# vtf-schem-v1.net
KiCad netlist of a schematic drawn in Altium Designer
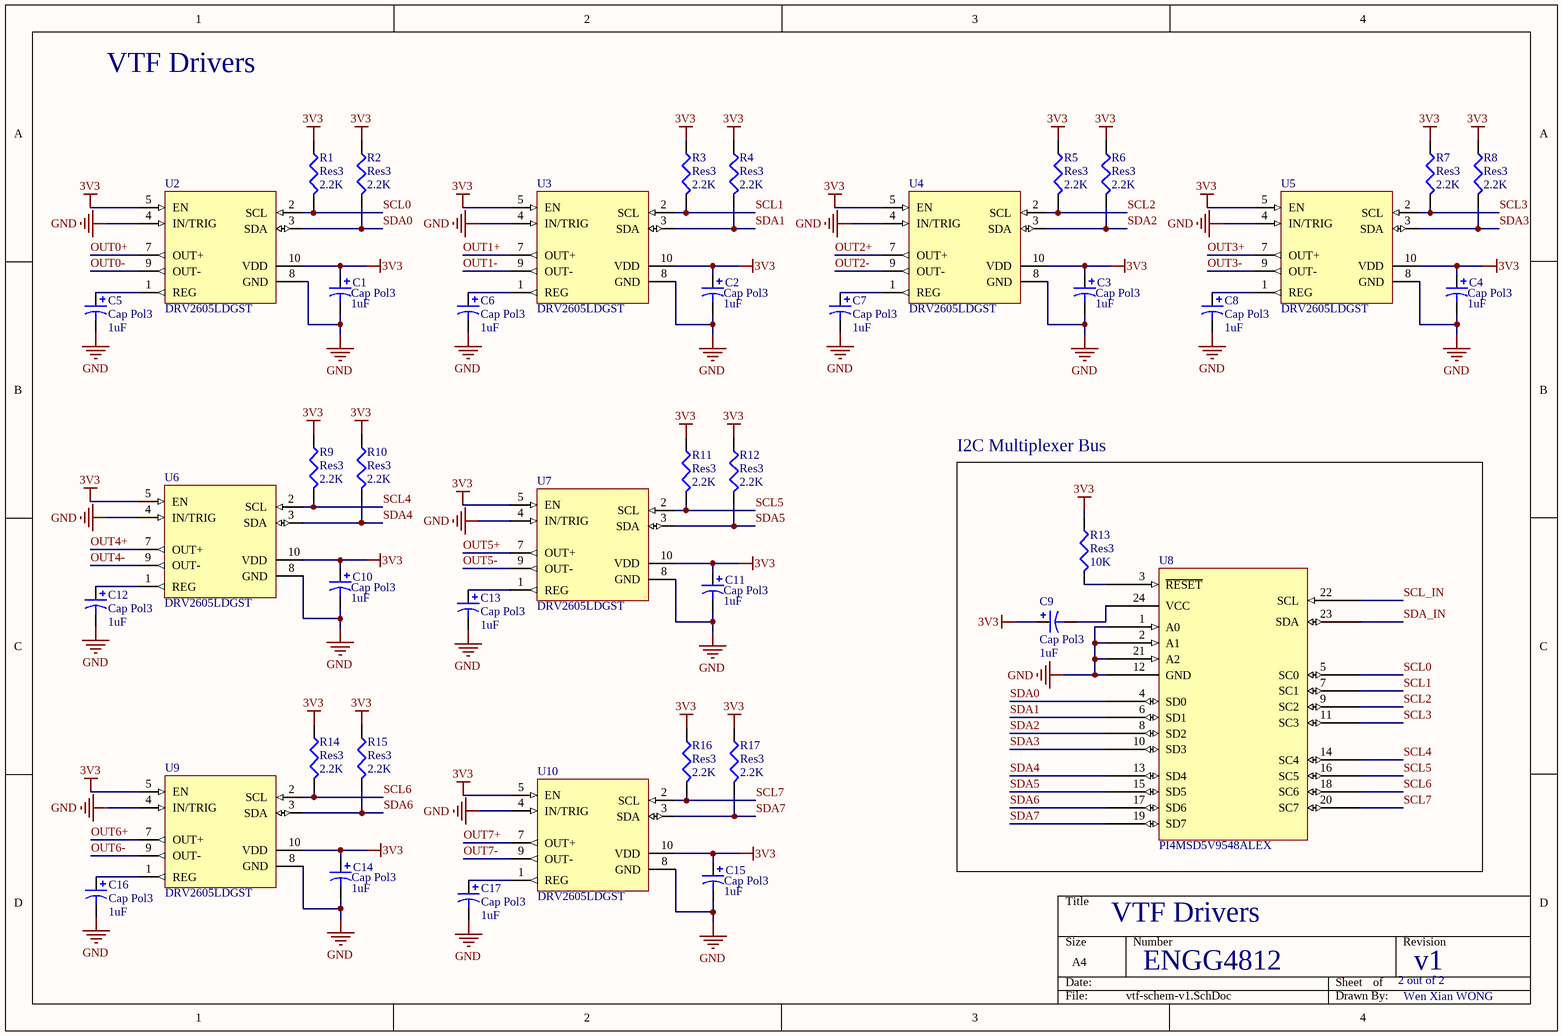
[diagram p0: vtf-schem-v1.SchDoc]

(export (version "E")
  (design (tool "Eeschema 10.0.6"))
  (components
    (comp (ref "C1")
      (value "Cap Pol3")
      (footprint "0402")
      (description "Polarized Capacitor (Surface Mount)")
      (fields (field (name "ALTIUM_VALUE") "1uF") (field (name "PUBLISHER") "Altium Limited"))
      (libsource (lib "Miscellaneous Devices") (part "Cap Pol3"))
    )
    (comp (ref "C2")
      (value "Cap Pol3")
      (footprint "0402")
      (description "Polarized Capacitor (Surface Mount)")
      (fields (field (name "ALTIUM_VALUE") "1uF") (field (name "PUBLISHER") "Altium Limited"))
      (libsource (lib "Miscellaneous Devices") (part "Cap Pol3"))
    )
    (comp (ref "C3")
      (value "Cap Pol3")
      (footprint "0402")
      (description "Polarized Capacitor (Surface Mount)")
      (fields (field (name "ALTIUM_VALUE") "1uF") (field (name "PUBLISHER") "Altium Limited"))
      (libsource (lib "Miscellaneous Devices") (part "Cap Pol3"))
    )
    (comp (ref "C4")
      (value "Cap Pol3")
      (footprint "0402")
      (description "Polarized Capacitor (Surface Mount)")
      (fields (field (name "ALTIUM_VALUE") "1uF") (field (name "PUBLISHER") "Altium Limited"))
      (libsource (lib "Miscellaneous Devices") (part "Cap Pol3"))
    )
    (comp (ref "C5")
      (value "Cap Pol3")
      (footprint "0402")
      (description "Polarized Capacitor (Surface Mount)")
      (fields (field (name "ALTIUM_VALUE") "1uF") (field (name "PUBLISHER") "Altium Limited"))
      (libsource (lib "Miscellaneous Devices") (part "Cap Pol3"))
    )
    (comp (ref "C6")
      (value "Cap Pol3")
      (footprint "0402")
      (description "Polarized Capacitor (Surface Mount)")
      (fields (field (name "ALTIUM_VALUE") "1uF") (field (name "PUBLISHER") "Altium Limited"))
      (libsource (lib "Miscellaneous Devices") (part "Cap Pol3"))
    )
    (comp (ref "C7")
      (value "Cap Pol3")
      (footprint "0402")
      (description "Polarized Capacitor (Surface Mount)")
      (fields (field (name "ALTIUM_VALUE") "1uF") (field (name "PUBLISHER") "Altium Limited"))
      (libsource (lib "Miscellaneous Devices") (part "Cap Pol3"))
    )
    (comp (ref "C8")
      (value "Cap Pol3")
      (footprint "0402")
      (description "Polarized Capacitor (Surface Mount)")
      (fields (field (name "ALTIUM_VALUE") "1uF") (field (name "PUBLISHER") "Altium Limited"))
      (libsource (lib "Miscellaneous Devices") (part "Cap Pol3"))
    )
    (comp (ref "C9")
      (value "Cap Pol3")
      (footprint "0402")
      (description "Polarized Capacitor (Surface Mount)")
      (fields (field (name "ALTIUM_VALUE") "1uF") (field (name "PUBLISHER") "Altium Limited"))
      (libsource (lib "Miscellaneous Devices") (part "Cap Pol3"))
    )
    (comp (ref "C10")
      (value "Cap Pol3")
      (footprint "0402")
      (description "Polarized Capacitor (Surface Mount)")
      (fields (field (name "ALTIUM_VALUE") "1uF") (field (name "PUBLISHER") "Altium Limited"))
      (libsource (lib "Miscellaneous Devices") (part "Cap Pol3"))
    )
    (comp (ref "C11")
      (value "Cap Pol3")
      (footprint "0402")
      (description "Polarized Capacitor (Surface Mount)")
      (fields (field (name "ALTIUM_VALUE") "1uF") (field (name "PUBLISHER") "Altium Limited"))
      (libsource (lib "Miscellaneous Devices") (part "Cap Pol3"))
    )
    (comp (ref "C12")
      (value "Cap Pol3")
      (footprint "0402")
      (description "Polarized Capacitor (Surface Mount)")
      (fields (field (name "ALTIUM_VALUE") "1uF") (field (name "PUBLISHER") "Altium Limited"))
      (libsource (lib "Miscellaneous Devices") (part "Cap Pol3"))
    )
    (comp (ref "C13")
      (value "Cap Pol3")
      (footprint "0402")
      (description "Polarized Capacitor (Surface Mount)")
      (fields (field (name "ALTIUM_VALUE") "1uF") (field (name "PUBLISHER") "Altium Limited"))
      (libsource (lib "Miscellaneous Devices") (part "Cap Pol3"))
    )
    (comp (ref "C14")
      (value "Cap Pol3")
      (footprint "0402")
      (description "Polarized Capacitor (Surface Mount)")
      (fields (field (name "ALTIUM_VALUE") "1uF") (field (name "PUBLISHER") "Altium Limited"))
      (libsource (lib "Miscellaneous Devices") (part "Cap Pol3"))
    )
    (comp (ref "C15")
      (value "Cap Pol3")
      (footprint "0402")
      (description "Polarized Capacitor (Surface Mount)")
      (fields (field (name "ALTIUM_VALUE") "1uF") (field (name "PUBLISHER") "Altium Limited"))
      (libsource (lib "Miscellaneous Devices") (part "Cap Pol3"))
    )
    (comp (ref "C16")
      (value "Cap Pol3")
      (footprint "0402")
      (description "Polarized Capacitor (Surface Mount)")
      (fields (field (name "ALTIUM_VALUE") "1uF") (field (name "PUBLISHER") "Altium Limited"))
      (libsource (lib "Miscellaneous Devices") (part "Cap Pol3"))
    )
    (comp (ref "C17")
      (value "Cap Pol3")
      (footprint "0402")
      (description "Polarized Capacitor (Surface Mount)")
      (fields (field (name "ALTIUM_VALUE") "1uF") (field (name "PUBLISHER") "Altium Limited"))
      (libsource (lib "Miscellaneous Devices") (part "Cap Pol3"))
    )
    (comp (ref "R1")
      (value "Res3")
      (footprint "0402")
      (description "Resistor")
      (fields (field (name "ALTIUM_VALUE") "2.2K") (field (name "PUBLISHER") "Altium Limited"))
      (libsource (lib "Miscellaneous Devices") (part "Res3"))
    )
    (comp (ref "R2")
      (value "Res3")
      (footprint "0402")
      (description "Resistor")
      (fields (field (name "ALTIUM_VALUE") "2.2K") (field (name "PUBLISHER") "Altium Limited"))
      (libsource (lib "Miscellaneous Devices") (part "Res3"))
    )
    (comp (ref "R3")
      (value "Res3")
      (footprint "0402")
      (description "Resistor")
      (fields (field (name "ALTIUM_VALUE") "2.2K") (field (name "PUBLISHER") "Altium Limited"))
      (libsource (lib "Miscellaneous Devices") (part "Res3"))
    )
    (comp (ref "R4")
      (value "Res3")
      (footprint "0402")
      (description "Resistor")
      (fields (field (name "ALTIUM_VALUE") "2.2K") (field (name "PUBLISHER") "Altium Limited"))
      (libsource (lib "Miscellaneous Devices") (part "Res3"))
    )
    (comp (ref "R5")
      (value "Res3")
      (footprint "0402")
      (description "Resistor")
      (fields (field (name "ALTIUM_VALUE") "2.2K") (field (name "PUBLISHER") "Altium Limited"))
      (libsource (lib "Miscellaneous Devices") (part "Res3"))
    )
    (comp (ref "R6")
      (value "Res3")
      (footprint "0402")
      (description "Resistor")
      (fields (field (name "ALTIUM_VALUE") "2.2K") (field (name "PUBLISHER") "Altium Limited"))
      (libsource (lib "Miscellaneous Devices") (part "Res3"))
    )
    (comp (ref "R7")
      (value "Res3")
      (footprint "0402")
      (description "Resistor")
      (fields (field (name "ALTIUM_VALUE") "2.2K") (field (name "PUBLISHER") "Altium Limited"))
      (libsource (lib "Miscellaneous Devices") (part "Res3"))
    )
    (comp (ref "R8")
      (value "Res3")
      (footprint "0402")
      (description "Resistor")
      (fields (field (name "ALTIUM_VALUE") "2.2K") (field (name "PUBLISHER") "Altium Limited"))
      (libsource (lib "Miscellaneous Devices") (part "Res3"))
    )
    (comp (ref "R9")
      (value "Res3")
      (footprint "0402")
      (description "Resistor")
      (fields (field (name "ALTIUM_VALUE") "2.2K") (field (name "PUBLISHER") "Altium Limited"))
      (libsource (lib "Miscellaneous Devices") (part "Res3"))
    )
    (comp (ref "R10")
      (value "Res3")
      (footprint "0402")
      (description "Resistor")
      (fields (field (name "ALTIUM_VALUE") "2.2K") (field (name "PUBLISHER") "Altium Limited"))
      (libsource (lib "Miscellaneous Devices") (part "Res3"))
    )
    (comp (ref "R11")
      (value "Res3")
      (footprint "0402")
      (description "Resistor")
      (fields (field (name "ALTIUM_VALUE") "2.2K") (field (name "PUBLISHER") "Altium Limited"))
      (libsource (lib "Miscellaneous Devices") (part "Res3"))
    )
    (comp (ref "R12")
      (value "Res3")
      (footprint "0402")
      (description "Resistor")
      (fields (field (name "ALTIUM_VALUE") "2.2K") (field (name "PUBLISHER") "Altium Limited"))
      (libsource (lib "Miscellaneous Devices") (part "Res3"))
    )
    (comp (ref "R13")
      (value "Res3")
      (footprint "0402")
      (description "Resistor")
      (fields (field (name "ALTIUM_VALUE") "10K") (field (name "PUBLISHER") "Altium Limited"))
      (libsource (lib "Miscellaneous Devices") (part "Res3"))
    )
    (comp (ref "R14")
      (value "Res3")
      (footprint "0402")
      (description "Resistor")
      (fields (field (name "ALTIUM_VALUE") "2.2K") (field (name "PUBLISHER") "Altium Limited"))
      (libsource (lib "Miscellaneous Devices") (part "Res3"))
    )
    (comp (ref "R15")
      (value "Res3")
      (footprint "0402")
      (description "Resistor")
      (fields (field (name "ALTIUM_VALUE") "2.2K") (field (name "PUBLISHER") "Altium Limited"))
      (libsource (lib "Miscellaneous Devices") (part "Res3"))
    )
    (comp (ref "R16")
      (value "Res3")
      (footprint "0402")
      (description "Resistor")
      (fields (field (name "ALTIUM_VALUE") "2.2K") (field (name "PUBLISHER") "Altium Limited"))
      (libsource (lib "Miscellaneous Devices") (part "Res3"))
    )
    (comp (ref "R17")
      (value "Res3")
      (footprint "0402")
      (description "Resistor")
      (fields (field (name "ALTIUM_VALUE") "2.2K") (field (name "PUBLISHER") "Altium Limited"))
      (libsource (lib "Miscellaneous Devices") (part "Res3"))
    )
    (comp (ref "U2")
      (value "DRV2605LDGST")
      (footprint "Driver")
      (libsource (lib "Schlib1") (part "DRV2605LDGST"))
    )
    (comp (ref "U3")
      (value "DRV2605LDGST")
      (footprint "Driver")
      (libsource (lib "Schlib1") (part "DRV2605LDGST"))
    )
    (comp (ref "U4")
      (value "DRV2605LDGST")
      (footprint "Driver")
      (libsource (lib "Schlib1") (part "DRV2605LDGST"))
    )
    (comp (ref "U5")
      (value "DRV2605LDGST")
      (footprint "Driver")
      (libsource (lib "Schlib1") (part "DRV2605LDGST"))
    )
    (comp (ref "U6")
      (value "DRV2605LDGST")
      (footprint "Driver")
      (libsource (lib "Schlib1") (part "DRV2605LDGST"))
    )
    (comp (ref "U7")
      (value "DRV2605LDGST")
      (footprint "Driver")
      (libsource (lib "Schlib1") (part "DRV2605LDGST"))
    )
    (comp (ref "U8")
      (value "PI4MSD5V9548ALEX")
      (footprint "I2C bus")
      (libsource (lib "Schlib1") (part "I2C Bus"))
    )
    (comp (ref "U9")
      (value "DRV2605LDGST")
      (footprint "Driver")
      (libsource (lib "Schlib1") (part "DRV2605LDGST"))
    )
    (comp (ref "U10")
      (value "DRV2605LDGST")
      (footprint "Driver")
      (libsource (lib "Schlib1") (part "DRV2605LDGST"))
    )
  )
  (nets
    (net (code "1") (name "/OUT0+") (class "Default")
      (node (ref "U2") (pin "7") (pinfunction "OUT+_7") (pintype "output"))
    )
    (net (code "2") (name "/OUT0-") (class "Default")
      (node (ref "U2") (pin "9") (pinfunction "OUT-_9") (pintype "output"))
    )
    (net (code "3") (name "/OUT1+") (class "Default")
      (node (ref "U3") (pin "7") (pinfunction "OUT+_7") (pintype "output"))
    )
    (net (code "4") (name "/OUT1-") (class "Default")
      (node (ref "U3") (pin "9") (pinfunction "OUT-_9") (pintype "output"))
    )
    (net (code "5") (name "/OUT2+") (class "Default")
      (node (ref "U4") (pin "7") (pinfunction "OUT+_7") (pintype "output"))
    )
    (net (code "6") (name "/OUT2-") (class "Default")
      (node (ref "U4") (pin "9") (pinfunction "OUT-_9") (pintype "output"))
    )
    (net (code "7") (name "/OUT3+") (class "Default")
      (node (ref "U5") (pin "7") (pinfunction "OUT+_7") (pintype "output"))
    )
    (net (code "8") (name "/OUT3-") (class "Default")
      (node (ref "U5") (pin "9") (pinfunction "OUT-_9") (pintype "output"))
    )
    (net (code "9") (name "/OUT4+") (class "Default")
      (node (ref "U6") (pin "7") (pinfunction "OUT+_7") (pintype "output"))
    )
    (net (code "10") (name "/OUT4-") (class "Default")
      (node (ref "U6") (pin "9") (pinfunction "OUT-_9") (pintype "output"))
    )
    (net (code "11") (name "/OUT5+") (class "Default")
      (node (ref "U7") (pin "7") (pinfunction "OUT+_7") (pintype "output"))
    )
    (net (code "12") (name "/OUT5-") (class "Default")
      (node (ref "U7") (pin "9") (pinfunction "OUT-_9") (pintype "output"))
    )
    (net (code "13") (name "/OUT6+") (class "Default")
      (node (ref "U9") (pin "7") (pinfunction "OUT+_7") (pintype "output"))
    )
    (net (code "14") (name "/OUT6-") (class "Default")
      (node (ref "U9") (pin "9") (pinfunction "OUT-_9") (pintype "output"))
    )
    (net (code "15") (name "/OUT7+") (class "Default")
      (node (ref "U10") (pin "7") (pinfunction "OUT+_7") (pintype "output"))
    )
    (net (code "16") (name "/OUT7-") (class "Default")
      (node (ref "U10") (pin "9") (pinfunction "OUT-_9") (pintype "output"))
    )
    (net (code "17") (name "/SCL0") (class "Default")
      (node (ref "R1") (pin "2") (pinfunction "2_2") (pintype "passive"))
      (node (ref "U2") (pin "2") (pinfunction "SCL_2") (pintype "input"))
      (node (ref "U8") (pin "5") (pinfunction "SC0_5") (pintype "bidirectional"))
    )
    (net (code "18") (name "/SCL1") (class "Default")
      (node (ref "R3") (pin "2") (pinfunction "2_2") (pintype "passive"))
      (node (ref "U3") (pin "2") (pinfunction "SCL_2") (pintype "input"))
      (node (ref "U8") (pin "7") (pinfunction "SC1_7") (pintype "bidirectional"))
    )
    (net (code "19") (name "/SCL2") (class "Default")
      (node (ref "R5") (pin "2") (pinfunction "2_2") (pintype "passive"))
      (node (ref "U4") (pin "2") (pinfunction "SCL_2") (pintype "input"))
      (node (ref "U8") (pin "9") (pinfunction "SC2_9") (pintype "bidirectional"))
    )
    (net (code "20") (name "/SCL3") (class "Default")
      (node (ref "R7") (pin "2") (pinfunction "2_2") (pintype "passive"))
      (node (ref "U5") (pin "2") (pinfunction "SCL_2") (pintype "input"))
      (node (ref "U8") (pin "11") (pinfunction "SC3_11") (pintype "bidirectional"))
    )
    (net (code "21") (name "/SCL4") (class "Default")
      (node (ref "R9") (pin "2") (pinfunction "2_2") (pintype "passive"))
      (node (ref "U6") (pin "2") (pinfunction "SCL_2") (pintype "input"))
      (node (ref "U8") (pin "14") (pinfunction "SC4_14") (pintype "bidirectional"))
    )
    (net (code "22") (name "/SCL5") (class "Default")
      (node (ref "R11") (pin "2") (pinfunction "2_2") (pintype "passive"))
      (node (ref "U7") (pin "2") (pinfunction "SCL_2") (pintype "input"))
      (node (ref "U8") (pin "16") (pinfunction "SC5_16") (pintype "bidirectional"))
    )
    (net (code "23") (name "/SCL6") (class "Default")
      (node (ref "R14") (pin "2") (pinfunction "2_2") (pintype "passive"))
      (node (ref "U8") (pin "18") (pinfunction "SC6_18") (pintype "bidirectional"))
      (node (ref "U9") (pin "2") (pinfunction "SCL_2") (pintype "input"))
    )
    (net (code "24") (name "/SCL7") (class "Default")
      (node (ref "R16") (pin "2") (pinfunction "2_2") (pintype "passive"))
      (node (ref "U10") (pin "2") (pinfunction "SCL_2") (pintype "input"))
      (node (ref "U8") (pin "20") (pinfunction "SC7_20") (pintype "bidirectional"))
    )
    (net (code "25") (name "/SCL_IN") (class "Default")
      (node (ref "U8") (pin "22") (pinfunction "SCL_22") (pintype "input"))
    )
    (net (code "26") (name "/SDA0") (class "Default")
      (node (ref "R2") (pin "2") (pinfunction "2_2") (pintype "passive"))
      (node (ref "U2") (pin "3") (pinfunction "SDA_3") (pintype "bidirectional"))
      (node (ref "U8") (pin "4") (pinfunction "SD0_4") (pintype "bidirectional"))
    )
    (net (code "27") (name "/SDA1") (class "Default")
      (node (ref "R4") (pin "2") (pinfunction "2_2") (pintype "passive"))
      (node (ref "U3") (pin "3") (pinfunction "SDA_3") (pintype "bidirectional"))
      (node (ref "U8") (pin "6") (pinfunction "SD1_6") (pintype "bidirectional"))
    )
    (net (code "28") (name "/SDA2") (class "Default")
      (node (ref "R6") (pin "2") (pinfunction "2_2") (pintype "passive"))
      (node (ref "U4") (pin "3") (pinfunction "SDA_3") (pintype "bidirectional"))
      (node (ref "U8") (pin "8") (pinfunction "SD2_8") (pintype "bidirectional"))
    )
    (net (code "29") (name "/SDA3") (class "Default")
      (node (ref "R8") (pin "2") (pinfunction "2_2") (pintype "passive"))
      (node (ref "U5") (pin "3") (pinfunction "SDA_3") (pintype "bidirectional"))
      (node (ref "U8") (pin "10") (pinfunction "SD3_10") (pintype "bidirectional"))
    )
    (net (code "30") (name "/SDA4") (class "Default")
      (node (ref "R10") (pin "2") (pinfunction "2_2") (pintype "passive"))
      (node (ref "U6") (pin "3") (pinfunction "SDA_3") (pintype "bidirectional"))
      (node (ref "U8") (pin "13") (pinfunction "SD4_13") (pintype "bidirectional"))
    )
    (net (code "31") (name "/SDA5") (class "Default")
      (node (ref "R12") (pin "2") (pinfunction "2_2") (pintype "passive"))
      (node (ref "U7") (pin "3") (pinfunction "SDA_3") (pintype "bidirectional"))
      (node (ref "U8") (pin "15") (pinfunction "SD5_15") (pintype "bidirectional"))
    )
    (net (code "32") (name "/SDA6") (class "Default")
      (node (ref "R15") (pin "2") (pinfunction "2_2") (pintype "passive"))
      (node (ref "U8") (pin "17") (pinfunction "SD6_17") (pintype "bidirectional"))
      (node (ref "U9") (pin "3") (pinfunction "SDA_3") (pintype "bidirectional"))
    )
    (net (code "33") (name "/SDA7") (class "Default")
      (node (ref "R17") (pin "2") (pinfunction "2_2") (pintype "passive"))
      (node (ref "U10") (pin "3") (pinfunction "SDA_3") (pintype "bidirectional"))
      (node (ref "U8") (pin "19") (pinfunction "SD7_19") (pintype "bidirectional"))
    )
    (net (code "34") (name "/SDA_IN") (class "Default")
      (node (ref "U8") (pin "23") (pinfunction "SDA_23") (pintype "bidirectional"))
    )
    (net (code "35") (name "3V3") (class "Default")
      (node (ref "C1") (pin "1") (pinfunction "1_1") (pintype "passive"))
      (node (ref "C10") (pin "1") (pinfunction "1_1") (pintype "passive"))
      (node (ref "C11") (pin "1") (pinfunction "1_1") (pintype "passive"))
      (node (ref "C14") (pin "1") (pinfunction "1_1") (pintype "passive"))
      (node (ref "C15") (pin "1") (pinfunction "1_1") (pintype "passive"))
      (node (ref "C2") (pin "1") (pinfunction "1_1") (pintype "passive"))
      (node (ref "C3") (pin "1") (pinfunction "1_1") (pintype "passive"))
      (node (ref "C4") (pin "1") (pinfunction "1_1") (pintype "passive"))
      (node (ref "C9") (pin "1") (pinfunction "1_1") (pintype "passive"))
      (node (ref "R1") (pin "1") (pinfunction "1_1") (pintype "passive"))
      (node (ref "R10") (pin "1") (pinfunction "1_1") (pintype "passive"))
      (node (ref "R11") (pin "1") (pinfunction "1_1") (pintype "passive"))
      (node (ref "R12") (pin "1") (pinfunction "1_1") (pintype "passive"))
      (node (ref "R13") (pin "1") (pinfunction "1_1") (pintype "passive"))
      (node (ref "R14") (pin "1") (pinfunction "1_1") (pintype "passive"))
      (node (ref "R15") (pin "1") (pinfunction "1_1") (pintype "passive"))
      (node (ref "R16") (pin "1") (pinfunction "1_1") (pintype "passive"))
      (node (ref "R17") (pin "1") (pinfunction "1_1") (pintype "passive"))
      (node (ref "R2") (pin "1") (pinfunction "1_1") (pintype "passive"))
      (node (ref "R3") (pin "1") (pinfunction "1_1") (pintype "passive"))
      (node (ref "R4") (pin "1") (pinfunction "1_1") (pintype "passive"))
      (node (ref "R5") (pin "1") (pinfunction "1_1") (pintype "passive"))
      (node (ref "R6") (pin "1") (pinfunction "1_1") (pintype "passive"))
      (node (ref "R7") (pin "1") (pinfunction "1_1") (pintype "passive"))
      (node (ref "R8") (pin "1") (pinfunction "1_1") (pintype "passive"))
      (node (ref "R9") (pin "1") (pinfunction "1_1") (pintype "passive"))
      (node (ref "U10") (pin "10") (pinfunction "VDD_10") (pintype "power_in"))
      (node (ref "U10") (pin "5") (pinfunction "EN_5") (pintype "input"))
      (node (ref "U2") (pin "10") (pinfunction "VDD_10") (pintype "power_in"))
      (node (ref "U2") (pin "5") (pinfunction "EN_5") (pintype "input"))
      (node (ref "U3") (pin "10") (pinfunction "VDD_10") (pintype "power_in"))
      (node (ref "U3") (pin "5") (pinfunction "EN_5") (pintype "input"))
      (node (ref "U4") (pin "10") (pinfunction "VDD_10") (pintype "power_in"))
      (node (ref "U4") (pin "5") (pinfunction "EN_5") (pintype "input"))
      (node (ref "U5") (pin "10") (pinfunction "VDD_10") (pintype "power_in"))
      (node (ref "U5") (pin "5") (pinfunction "EN_5") (pintype "input"))
      (node (ref "U6") (pin "10") (pinfunction "VDD_10") (pintype "power_in"))
      (node (ref "U6") (pin "5") (pinfunction "EN_5") (pintype "input"))
      (node (ref "U7") (pin "10") (pinfunction "VDD_10") (pintype "power_in"))
      (node (ref "U7") (pin "5") (pinfunction "EN_5") (pintype "input"))
      (node (ref "U9") (pin "10") (pinfunction "VDD_10") (pintype "power_in"))
      (node (ref "U9") (pin "5") (pinfunction "EN_5") (pintype "input"))
    )
    (net (code "36") (name "GND") (class "Default")
      (node (ref "C1") (pin "2") (pinfunction "2_2") (pintype "passive"))
      (node (ref "C10") (pin "2") (pinfunction "2_2") (pintype "passive"))
      (node (ref "C11") (pin "2") (pinfunction "2_2") (pintype "passive"))
      (node (ref "C12") (pin "2") (pinfunction "2_2") (pintype "passive"))
      (node (ref "C13") (pin "2") (pinfunction "2_2") (pintype "passive"))
      (node (ref "C14") (pin "2") (pinfunction "2_2") (pintype "passive"))
      (node (ref "C15") (pin "2") (pinfunction "2_2") (pintype "passive"))
      (node (ref "C16") (pin "2") (pinfunction "2_2") (pintype "passive"))
      (node (ref "C17") (pin "2") (pinfunction "2_2") (pintype "passive"))
      (node (ref "C2") (pin "2") (pinfunction "2_2") (pintype "passive"))
      (node (ref "C3") (pin "2") (pinfunction "2_2") (pintype "passive"))
      (node (ref "C4") (pin "2") (pinfunction "2_2") (pintype "passive"))
      (node (ref "C5") (pin "2") (pinfunction "2_2") (pintype "passive"))
      (node (ref "C6") (pin "2") (pinfunction "2_2") (pintype "passive"))
      (node (ref "C7") (pin "2") (pinfunction "2_2") (pintype "passive"))
      (node (ref "C8") (pin "2") (pinfunction "2_2") (pintype "passive"))
      (node (ref "U10") (pin "4") (pinfunction "IN/TRIG_4") (pintype "input"))
      (node (ref "U10") (pin "8") (pinfunction "GND_8") (pintype "power_in"))
      (node (ref "U2") (pin "4") (pinfunction "IN/TRIG_4") (pintype "input"))
      (node (ref "U2") (pin "8") (pinfunction "GND_8") (pintype "power_in"))
      (node (ref "U3") (pin "4") (pinfunction "IN/TRIG_4") (pintype "input"))
      (node (ref "U3") (pin "8") (pinfunction "GND_8") (pintype "power_in"))
      (node (ref "U4") (pin "4") (pinfunction "IN/TRIG_4") (pintype "input"))
      (node (ref "U4") (pin "8") (pinfunction "GND_8") (pintype "power_in"))
      (node (ref "U5") (pin "4") (pinfunction "IN/TRIG_4") (pintype "input"))
      (node (ref "U5") (pin "8") (pinfunction "GND_8") (pintype "power_in"))
      (node (ref "U6") (pin "4") (pinfunction "IN/TRIG_4") (pintype "input"))
      (node (ref "U6") (pin "8") (pinfunction "GND_8") (pintype "power_in"))
      (node (ref "U7") (pin "4") (pinfunction "IN/TRIG_4") (pintype "input"))
      (node (ref "U7") (pin "8") (pinfunction "GND_8") (pintype "power_in"))
      (node (ref "U8") (pin "1") (pinfunction "A0_1") (pintype "input"))
      (node (ref "U8") (pin "12") (pinfunction "GND_12") (pintype "passive"))
      (node (ref "U8") (pin "2") (pinfunction "A1_2") (pintype "input"))
      (node (ref "U8") (pin "21") (pinfunction "A2_21") (pintype "input"))
      (node (ref "U9") (pin "4") (pinfunction "IN/TRIG_4") (pintype "input"))
      (node (ref "U9") (pin "8") (pinfunction "GND_8") (pintype "power_in"))
    )
    (net (code "37") (name "Net-(U2-REG)") (class "Default")
      (node (ref "C5") (pin "1") (pinfunction "1_1") (pintype "passive"))
      (node (ref "U2") (pin "1") (pinfunction "REG_1") (pintype "output"))
    )
    (net (code "38") (name "Net-(U3-REG)") (class "Default")
      (node (ref "C6") (pin "1") (pinfunction "1_1") (pintype "passive"))
      (node (ref "U3") (pin "1") (pinfunction "REG_1") (pintype "output"))
    )
    (net (code "39") (name "Net-(U4-REG)") (class "Default")
      (node (ref "C7") (pin "1") (pinfunction "1_1") (pintype "passive"))
      (node (ref "U4") (pin "1") (pinfunction "REG_1") (pintype "output"))
    )
    (net (code "40") (name "Net-(U5-REG)") (class "Default")
      (node (ref "C8") (pin "1") (pinfunction "1_1") (pintype "passive"))
      (node (ref "U5") (pin "1") (pinfunction "REG_1") (pintype "output"))
    )
    (net (code "41") (name "Net-(U6-REG)") (class "Default")
      (node (ref "C12") (pin "1") (pinfunction "1_1") (pintype "passive"))
      (node (ref "U6") (pin "1") (pinfunction "REG_1") (pintype "output"))
    )
    (net (code "42") (name "Net-(U7-REG)") (class "Default")
      (node (ref "C13") (pin "1") (pinfunction "1_1") (pintype "passive"))
      (node (ref "U7") (pin "1") (pinfunction "REG_1") (pintype "output"))
    )
    (net (code "43") (name "Net-(U8-VCC)") (class "Default")
      (node (ref "C9") (pin "2") (pinfunction "2_2") (pintype "passive"))
      (node (ref "U8") (pin "24") (pinfunction "VCC_24") (pintype "power_in"))
    )
    (net (code "44") (name "Net-(U8-~{RESET})") (class "Default")
      (node (ref "R13") (pin "2") (pinfunction "2_2") (pintype "passive"))
      (node (ref "U8") (pin "3") (pinfunction "~{RESET}_3") (pintype "input"))
    )
    (net (code "45") (name "Net-(U9-REG)") (class "Default")
      (node (ref "C16") (pin "1") (pinfunction "1_1") (pintype "passive"))
      (node (ref "U9") (pin "1") (pinfunction "REG_1") (pintype "output"))
    )
    (net (code "46") (name "Net-(U10-REG)") (class "Default")
      (node (ref "C17") (pin "1") (pinfunction "1_1") (pintype "passive"))
      (node (ref "U10") (pin "1") (pinfunction "REG_1") (pintype "output"))
    )
  )
)
